# Motor.net
KiCad netlist of a schematic drawn in Altium Designer
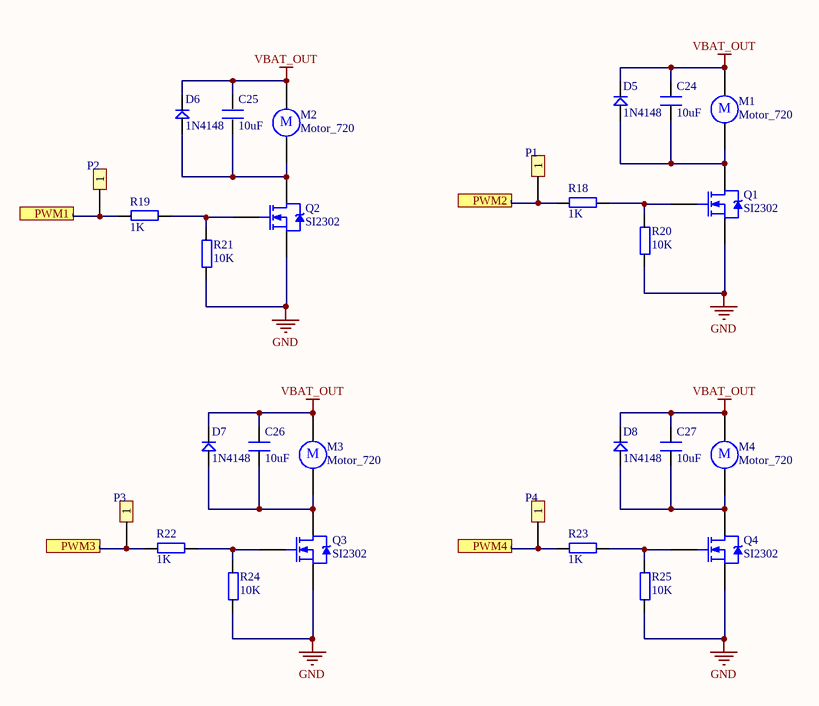
[diagram p0: Motor.SchDoc]

(export (version "E")
  (design (tool "Eeschema 10.0.6"))
  (components
    (comp (ref "C24") (value "10uF") (footprint "0603P") (libsource (lib "Explorer STM32F407封装库") (part "C")))
    (comp (ref "C25") (value "10uF") (footprint "0603P") (libsource (lib "Explorer STM32F407封装库") (part "C")))
    (comp (ref "C26") (value "10uF") (footprint "0603P") (libsource (lib "Explorer STM32F407封装库") (part "C")))
    (comp (ref "C27") (value "10uF") (footprint "0603P") (libsource (lib "Explorer STM32F407封装库") (part "C")))
    (comp (ref "D5")
      (value "1N4148")
      (footprint "DIODE_SOP")
      (libsource (lib "Explorer STM32F407封装库") (part "D"))
    )
    (comp (ref "D6")
      (value "1N4148")
      (footprint "DIODE_SOP")
      (libsource (lib "Explorer STM32F407封装库") (part "D"))
    )
    (comp (ref "D7")
      (value "1N4148")
      (footprint "DIODE_SOP")
      (libsource (lib "Explorer STM32F407封装库") (part "D"))
    )
    (comp (ref "D8")
      (value "1N4148")
      (footprint "DIODE_SOP")
      (libsource (lib "Explorer STM32F407封装库") (part "D"))
    )
    (comp (ref "M1")
      (value "Motor_720")
      (footprint "MOTOR")
      (description "Motor, General Kind")
      (fields (field (name "PUBLISHER") "mazhongwei"))
      (libsource (lib "RoboFly") (part "Motor_720"))
    )
    (comp (ref "M2")
      (value "Motor_720")
      (footprint "MOTOR")
      (description "Motor, General Kind")
      (fields (field (name "PUBLISHER") "mazhongwei"))
      (libsource (lib "RoboFly") (part "Motor_720"))
    )
    (comp (ref "M3")
      (value "Motor_720")
      (footprint "MOTOR")
      (description "Motor, General Kind")
      (fields (field (name "PUBLISHER") "mazhongwei"))
      (libsource (lib "RoboFly") (part "Motor_720"))
    )
    (comp (ref "M4")
      (value "Motor_720")
      (footprint "MOTOR")
      (description "Motor, General Kind")
      (fields (field (name "PUBLISHER") "mazhongwei"))
      (libsource (lib "RoboFly") (part "Motor_720"))
    )
    (comp (ref "P1")
      (value "Header 1")
      (footprint "HEADER1")
      (fields (field (name "PUBLISHER") "Altium Limited"))
      (libsource (lib "RoboFly") (part "Header 1"))
    )
    (comp (ref "P2")
      (value "Header 1")
      (footprint "HEADER1")
      (fields (field (name "PUBLISHER") "Altium Limited"))
      (libsource (lib "RoboFly") (part "Header 1"))
    )
    (comp (ref "P3")
      (value "Header 1")
      (footprint "HEADER1")
      (fields (field (name "PUBLISHER") "Altium Limited"))
      (libsource (lib "RoboFly") (part "Header 1"))
    )
    (comp (ref "P4")
      (value "Header 1")
      (footprint "HEADER1")
      (fields (field (name "PUBLISHER") "Altium Limited"))
      (libsource (lib "RoboFly") (part "Header 1"))
    )
    (comp (ref "Q1")
      (value "SI2302")
      (footprint "RoboFly:SOT23-3M")
      (description "N-Channel Power MOSFET")
      (fields (field (name "PUBLISHER") "mazhongwei"))
      (libsource (lib "RoboFly") (part "SI2302"))
    )
    (comp (ref "Q2")
      (value "SI2302")
      (footprint "RoboFly:SOT23-3M")
      (description "N-Channel Power MOSFET")
      (fields (field (name "PUBLISHER") "mazhongwei"))
      (libsource (lib "RoboFly") (part "SI2302"))
    )
    (comp (ref "Q3")
      (value "SI2302")
      (footprint "RoboFly:SOT23-3M")
      (description "N-Channel Power MOSFET")
      (fields (field (name "PUBLISHER") "mazhongwei"))
      (libsource (lib "RoboFly") (part "SI2302"))
    )
    (comp (ref "Q4")
      (value "SI2302")
      (footprint "RoboFly:SOT23-3M")
      (description "N-Channel Power MOSFET")
      (fields (field (name "PUBLISHER") "mazhongwei"))
      (libsource (lib "RoboFly") (part "SI2302"))
    )
    (comp (ref "R18") (value "1K") (footprint "0603P") (libsource (lib "Explorer STM32F407封装库") (part "R")))
    (comp (ref "R19") (value "1K") (footprint "0603P") (libsource (lib "Explorer STM32F407封装库") (part "R")))
    (comp (ref "R20") (value "10K") (footprint "0603P") (libsource (lib "Explorer STM32F407封装库") (part "R")))
    (comp (ref "R21") (value "10K") (footprint "0603P") (libsource (lib "Explorer STM32F407封装库") (part "R")))
    (comp (ref "R22") (value "1K") (footprint "0603P") (libsource (lib "Explorer STM32F407封装库") (part "R")))
    (comp (ref "R23") (value "1K") (footprint "0603P") (libsource (lib "Explorer STM32F407封装库") (part "R")))
    (comp (ref "R24") (value "10K") (footprint "0603P") (libsource (lib "Explorer STM32F407封装库") (part "R")))
    (comp (ref "R25") (value "10K") (footprint "0603P") (libsource (lib "Explorer STM32F407封装库") (part "R")))
  )
  (nets
    (net (code "1") (name "/PWM1") (class "Default")
      (node (ref "P2") (pin "1") (pinfunction "1_1") (pintype "passive"))
      (node (ref "R19") (pin "2") (pintype "passive"))
    )
    (net (code "2") (name "/PWM2") (class "Default")
      (node (ref "P1") (pin "1") (pinfunction "1_1") (pintype "passive"))
      (node (ref "R18") (pin "2") (pintype "passive"))
    )
    (net (code "3") (name "/PWM3") (class "Default")
      (node (ref "P3") (pin "1") (pinfunction "1_1") (pintype "passive"))
      (node (ref "R22") (pin "2") (pintype "passive"))
    )
    (net (code "4") (name "/PWM4") (class "Default")
      (node (ref "P4") (pin "1") (pinfunction "1_1") (pintype "passive"))
      (node (ref "R23") (pin "2") (pintype "passive"))
    )
    (net (code "5") (name "GND") (class "Default")
      (node (ref "Q1") (pin "2") (pinfunction "S_2") (pintype "passive"))
      (node (ref "Q2") (pin "2") (pinfunction "S_2") (pintype "passive"))
      (node (ref "Q3") (pin "2") (pinfunction "S_2") (pintype "passive"))
      (node (ref "Q4") (pin "2") (pinfunction "S_2") (pintype "passive"))
      (node (ref "R20") (pin "1") (pintype "passive"))
      (node (ref "R21") (pin "1") (pintype "passive"))
      (node (ref "R24") (pin "1") (pintype "passive"))
      (node (ref "R25") (pin "1") (pintype "passive"))
    )
    (net (code "6") (name "Net-(Q1-D)") (class "Default")
      (node (ref "C24") (pin "1") (pintype "passive"))
      (node (ref "D5") (pin "1") (pintype "passive"))
      (node (ref "M1") (pin "2") (pinfunction "2_2") (pintype "passive"))
      (node (ref "Q1") (pin "3") (pinfunction "D_3") (pintype "passive"))
    )
    (net (code "7") (name "Net-(Q1-G)") (class "Default")
      (node (ref "Q1") (pin "1") (pinfunction "G_1") (pintype "passive"))
      (node (ref "R18") (pin "1") (pintype "passive"))
      (node (ref "R20") (pin "2") (pintype "passive"))
    )
    (net (code "8") (name "Net-(Q2-D)") (class "Default")
      (node (ref "C25") (pin "1") (pintype "passive"))
      (node (ref "D6") (pin "1") (pintype "passive"))
      (node (ref "M2") (pin "2") (pinfunction "2_2") (pintype "passive"))
      (node (ref "Q2") (pin "3") (pinfunction "D_3") (pintype "passive"))
    )
    (net (code "9") (name "Net-(Q2-G)") (class "Default")
      (node (ref "Q2") (pin "1") (pinfunction "G_1") (pintype "passive"))
      (node (ref "R19") (pin "1") (pintype "passive"))
      (node (ref "R21") (pin "2") (pintype "passive"))
    )
    (net (code "10") (name "Net-(Q3-D)") (class "Default")
      (node (ref "C26") (pin "1") (pintype "passive"))
      (node (ref "D7") (pin "1") (pintype "passive"))
      (node (ref "M3") (pin "2") (pinfunction "2_2") (pintype "passive"))
      (node (ref "Q3") (pin "3") (pinfunction "D_3") (pintype "passive"))
    )
    (net (code "11") (name "Net-(Q3-G)") (class "Default")
      (node (ref "Q3") (pin "1") (pinfunction "G_1") (pintype "passive"))
      (node (ref "R22") (pin "1") (pintype "passive"))
      (node (ref "R24") (pin "2") (pintype "passive"))
    )
    (net (code "12") (name "Net-(Q4-D)") (class "Default")
      (node (ref "C27") (pin "1") (pintype "passive"))
      (node (ref "D8") (pin "1") (pintype "passive"))
      (node (ref "M4") (pin "2") (pinfunction "2_2") (pintype "passive"))
      (node (ref "Q4") (pin "3") (pinfunction "D_3") (pintype "passive"))
    )
    (net (code "13") (name "Net-(Q4-G)") (class "Default")
      (node (ref "Q4") (pin "1") (pinfunction "G_1") (pintype "passive"))
      (node (ref "R23") (pin "1") (pintype "passive"))
      (node (ref "R25") (pin "2") (pintype "passive"))
    )
    (net (code "14") (name "VBAT_OUT") (class "Default")
      (node (ref "C24") (pin "2") (pintype "passive"))
      (node (ref "C25") (pin "2") (pintype "passive"))
      (node (ref "C26") (pin "2") (pintype "passive"))
      (node (ref "C27") (pin "2") (pintype "passive"))
      (node (ref "D5") (pin "2") (pintype "passive"))
      (node (ref "D6") (pin "2") (pintype "passive"))
      (node (ref "D7") (pin "2") (pintype "passive"))
      (node (ref "D8") (pin "2") (pintype "passive"))
      (node (ref "M1") (pin "1") (pinfunction "1_1") (pintype "passive"))
      (node (ref "M2") (pin "1") (pinfunction "1_1") (pintype "passive"))
      (node (ref "M3") (pin "1") (pinfunction "1_1") (pintype "passive"))
      (node (ref "M4") (pin "1") (pinfunction "1_1") (pintype "passive"))
    )
  )
)
